# EmergencyCaller.net
KiCad netlist of a schematic drawn in Altium Designer
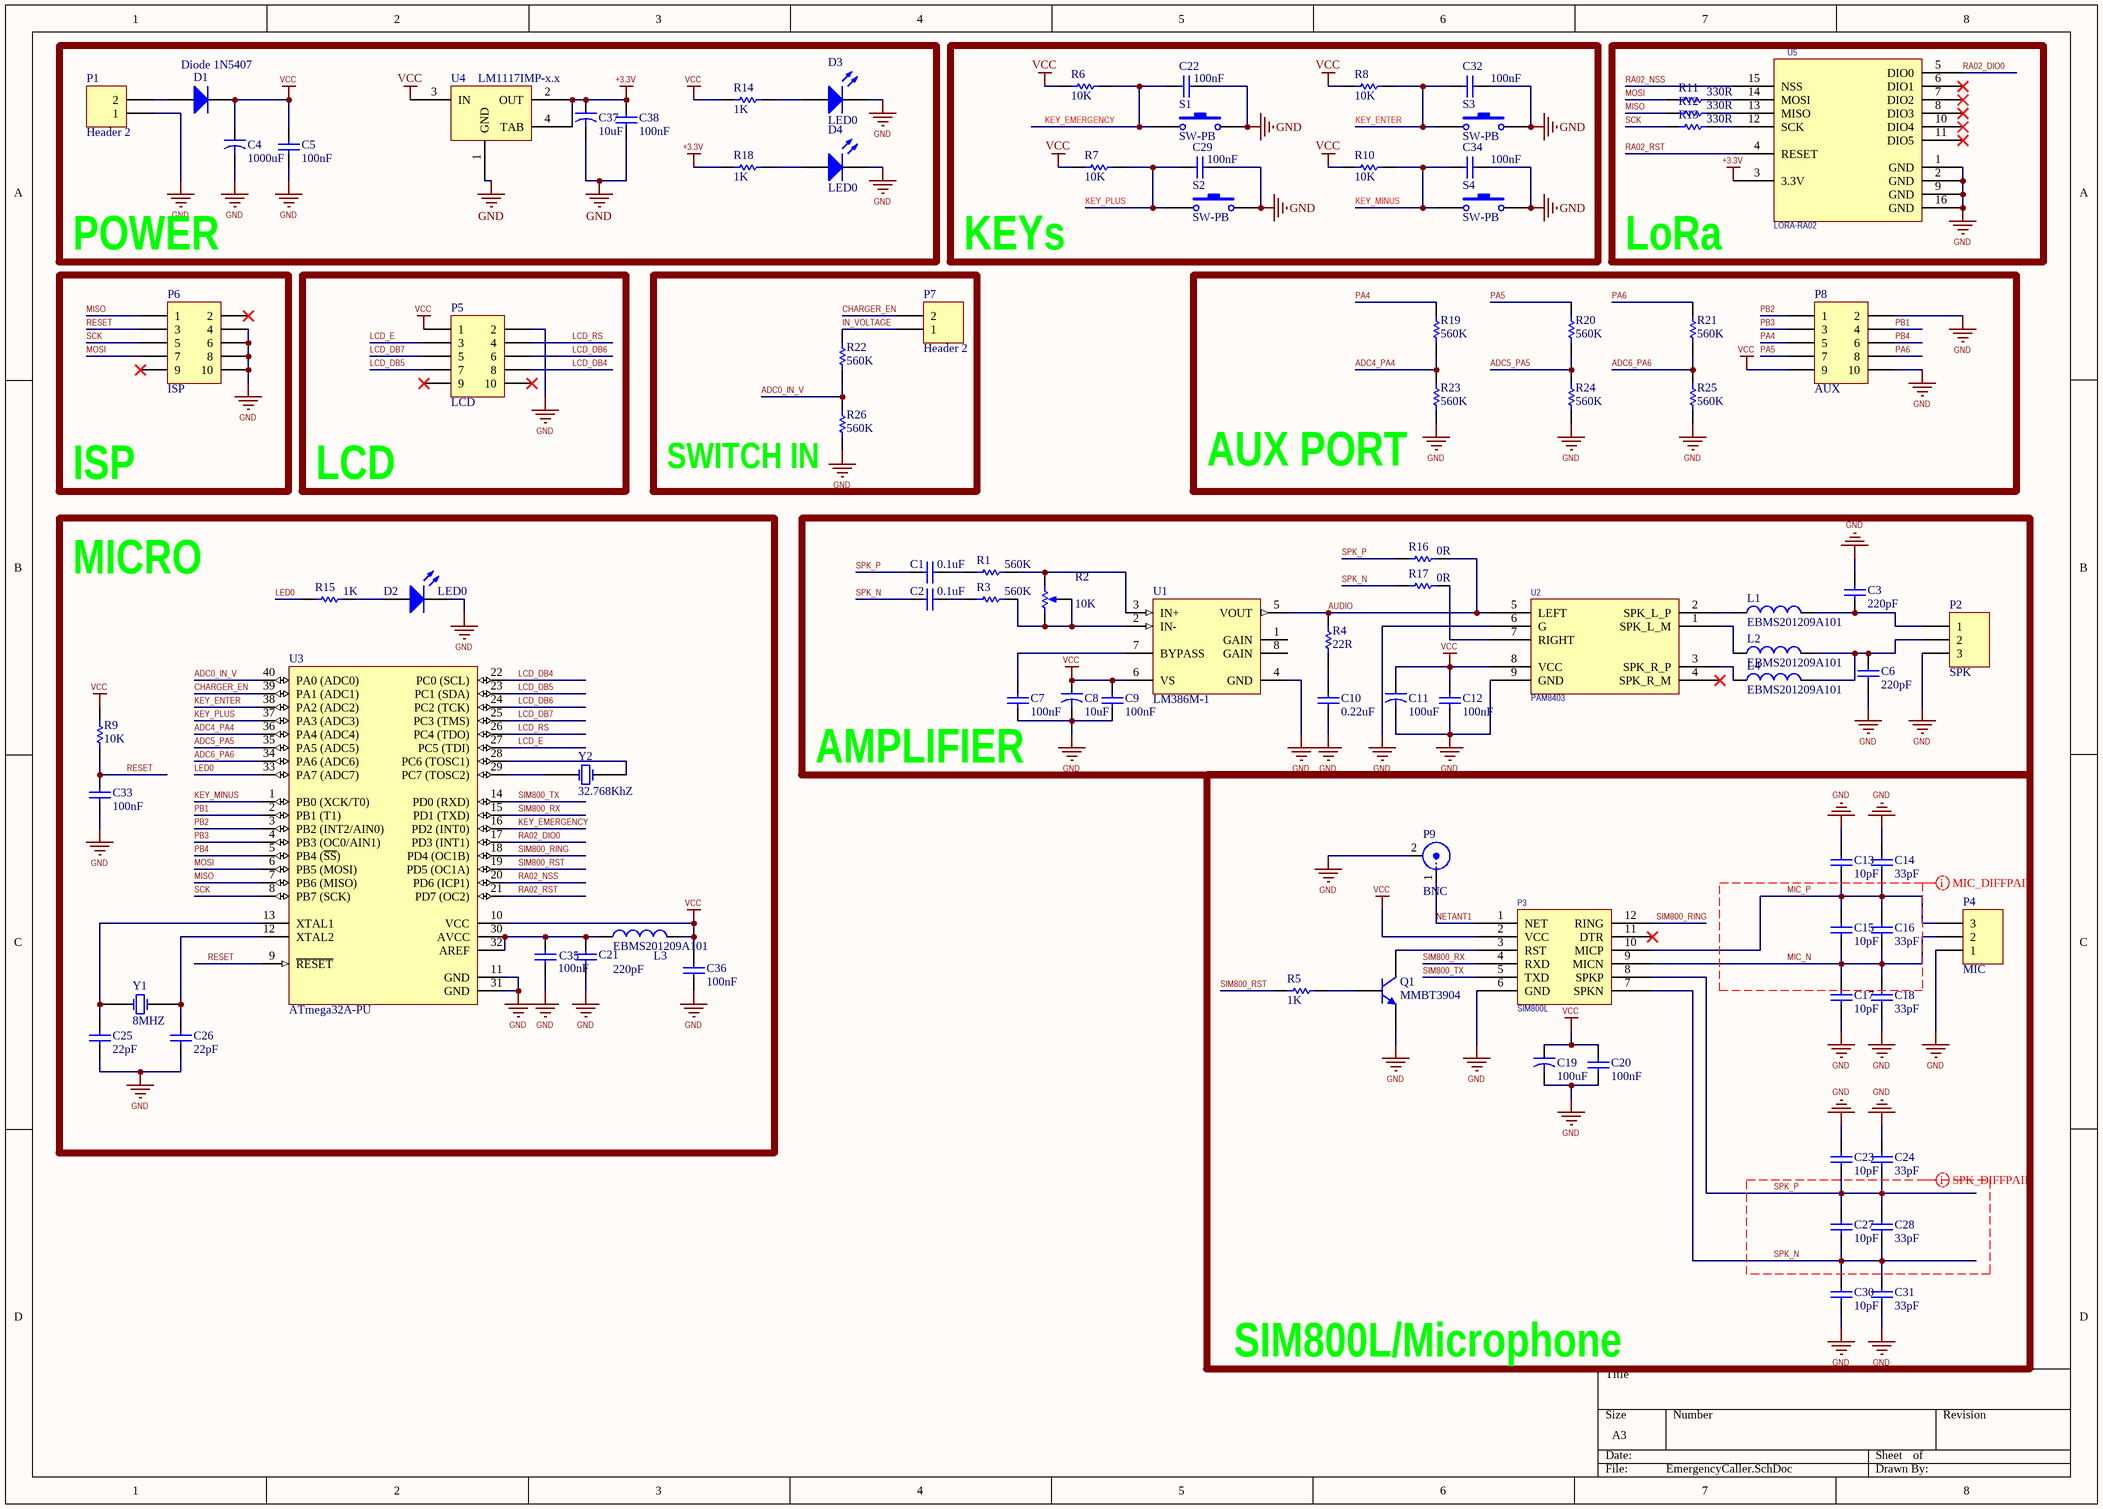
[diagram p0: EmergencyCaller.SchDoc]

(export (version "E")
  (design (tool "Eeschema 10.0.6"))
  (components
    (comp (ref "C1")
      (value "0.1uF")
      (footprint "CAP0805")
      (description "Capacitor")
      (fields (field (name "PUBLISHER") "Altium Limited"))
      (libsource (lib "Miscellaneous Devices") (part "Cap"))
    )
    (comp (ref "C2")
      (value "0.1uF")
      (footprint "CAP0805")
      (description "Capacitor")
      (fields (field (name "PUBLISHER") "Altium Limited"))
      (libsource (lib "Miscellaneous Devices") (part "Cap"))
    )
    (comp (ref "C3")
      (value "220pF")
      (footprint "CAP0805")
      (description "Capacitor")
      (fields (field (name "PUBLISHER") "Altium Limited"))
      (libsource (lib "Miscellaneous Devices") (part "Cap"))
    )
    (comp (ref "C4")
      (value "1000uF")
      (footprint "Cap electrolitic radial 10x16-5")
      (description "Capacitor")
      (fields (field (name "PUBLISHER") "Altium Limited"))
      (libsource (lib "Miscellaneous Devices") (part "Cap2"))
    )
    (comp (ref "C5")
      (value "100nF")
      (footprint "CAP0805")
      (description "Capacitor")
      (fields (field (name "PUBLISHER") "Altium Limited"))
      (libsource (lib "Miscellaneous Devices") (part "Cap"))
    )
    (comp (ref "C6")
      (value "220pF")
      (footprint "CAP0805")
      (description "Capacitor")
      (fields (field (name "PUBLISHER") "Altium Limited"))
      (libsource (lib "Miscellaneous Devices") (part "Cap"))
    )
    (comp (ref "C7")
      (value "100nF")
      (footprint "CAP0805")
      (description "Capacitor")
      (fields (field (name "PUBLISHER") "Altium Limited"))
      (libsource (lib "Miscellaneous Devices") (part "Cap"))
    )
    (comp (ref "C8")
      (value "10uF")
      (footprint "Cap electrolitic radial 5x11-2")
      (description "Capacitor")
      (fields (field (name "PUBLISHER") "Altium Limited"))
      (libsource (lib "Miscellaneous Devices") (part "Cap2"))
    )
    (comp (ref "C9")
      (value "100nF")
      (footprint "CAP0805")
      (description "Capacitor")
      (fields (field (name "PUBLISHER") "Altium Limited"))
      (libsource (lib "Miscellaneous Devices") (part "Cap"))
    )
    (comp (ref "C10")
      (value "0.22uF")
      (footprint "CAP0805")
      (description "Capacitor")
      (fields (field (name "PUBLISHER") "Altium Limited"))
      (libsource (lib "Miscellaneous Devices") (part "Cap"))
    )
    (comp (ref "C11")
      (value "100uF")
      (footprint "Cap electrolitic radial 10x16-5")
      (description "Capacitor")
      (fields (field (name "PUBLISHER") "Altium Limited"))
      (libsource (lib "Miscellaneous Devices") (part "Cap2"))
    )
    (comp (ref "C12")
      (value "100nF")
      (footprint "CAP0805")
      (description "Capacitor")
      (fields (field (name "PUBLISHER") "Altium Limited"))
      (libsource (lib "Miscellaneous Devices") (part "Cap"))
    )
    (comp (ref "C13")
      (value "10pF")
      (footprint "CAP0805")
      (description "Capacitor")
      (fields (field (name "PUBLISHER") "Altium Limited"))
      (libsource (lib "Miscellaneous Devices") (part "Cap"))
    )
    (comp (ref "C14")
      (value "33pF")
      (footprint "CAP0805")
      (description "Capacitor")
      (fields (field (name "PUBLISHER") "Altium Limited"))
      (libsource (lib "Miscellaneous Devices") (part "Cap"))
    )
    (comp (ref "C15")
      (value "10pF")
      (footprint "CAP0805")
      (description "Capacitor")
      (fields (field (name "PUBLISHER") "Altium Limited"))
      (libsource (lib "Miscellaneous Devices") (part "Cap"))
    )
    (comp (ref "C16")
      (value "33pF")
      (footprint "CAP0805")
      (description "Capacitor")
      (fields (field (name "PUBLISHER") "Altium Limited"))
      (libsource (lib "Miscellaneous Devices") (part "Cap"))
    )
    (comp (ref "C17")
      (value "10pF")
      (footprint "CAP0805")
      (description "Capacitor")
      (fields (field (name "PUBLISHER") "Altium Limited"))
      (libsource (lib "Miscellaneous Devices") (part "Cap"))
    )
    (comp (ref "C18")
      (value "33pF")
      (footprint "CAP0805")
      (description "Capacitor")
      (fields (field (name "PUBLISHER") "Altium Limited"))
      (libsource (lib "Miscellaneous Devices") (part "Cap"))
    )
    (comp (ref "C19")
      (value "100uF")
      (footprint "Cap electrolitic radial 10x16-5")
      (description "Capacitor")
      (fields (field (name "PUBLISHER") "Altium Limited"))
      (libsource (lib "Miscellaneous Devices") (part "Cap2"))
    )
    (comp (ref "C20")
      (value "100nF")
      (footprint "CAP0805")
      (description "Capacitor")
      (fields (field (name "PUBLISHER") "Altium Limited"))
      (libsource (lib "Miscellaneous Devices") (part "Cap"))
    )
    (comp (ref "C21")
      (value "220pF")
      (footprint "CAP0805")
      (description "Capacitor")
      (fields (field (name "PUBLISHER") "Altium Limited"))
      (libsource (lib "Miscellaneous Devices") (part "Cap"))
    )
    (comp (ref "C22")
      (value "100nF")
      (footprint "CAP0805")
      (description "Capacitor")
      (fields (field (name "Comment") "Cap") (field (name "PUBLISHER") "Altium Limited"))
      (libsource (lib "Miscellaneous Devices") (part "Cap"))
    )
    (comp (ref "C23")
      (value "10pF")
      (footprint "CAP0805")
      (description "Capacitor")
      (fields (field (name "PUBLISHER") "Altium Limited"))
      (libsource (lib "Miscellaneous Devices") (part "Cap"))
    )
    (comp (ref "C24")
      (value "33pF")
      (footprint "CAP0805")
      (description "Capacitor")
      (fields (field (name "PUBLISHER") "Altium Limited"))
      (libsource (lib "Miscellaneous Devices") (part "Cap"))
    )
    (comp (ref "C25")
      (value "22pF")
      (footprint "CAP0805")
      (description "Capacitor")
      (fields (field (name "PUBLISHER") "Altium Limited"))
      (libsource (lib "Miscellaneous Devices") (part "Cap"))
    )
    (comp (ref "C26")
      (value "22pF")
      (footprint "CAP0805")
      (description "Capacitor")
      (fields (field (name "PUBLISHER") "Altium Limited"))
      (libsource (lib "Miscellaneous Devices") (part "Cap"))
    )
    (comp (ref "C27")
      (value "10pF")
      (footprint "CAP0805")
      (description "Capacitor")
      (fields (field (name "PUBLISHER") "Altium Limited"))
      (libsource (lib "Miscellaneous Devices") (part "Cap"))
    )
    (comp (ref "C28")
      (value "33pF")
      (footprint "CAP0805")
      (description "Capacitor")
      (fields (field (name "PUBLISHER") "Altium Limited"))
      (libsource (lib "Miscellaneous Devices") (part "Cap"))
    )
    (comp (ref "C29")
      (value "100nF")
      (footprint "CAP0805")
      (description "Capacitor")
      (fields (field (name "Comment") "Cap") (field (name "PUBLISHER") "Altium Limited"))
      (libsource (lib "Miscellaneous Devices") (part "Cap"))
    )
    (comp (ref "C30")
      (value "10pF")
      (footprint "CAP0805")
      (description "Capacitor")
      (fields (field (name "PUBLISHER") "Altium Limited"))
      (libsource (lib "Miscellaneous Devices") (part "Cap"))
    )
    (comp (ref "C31")
      (value "33pF")
      (footprint "CAP0805")
      (description "Capacitor")
      (fields (field (name "PUBLISHER") "Altium Limited"))
      (libsource (lib "Miscellaneous Devices") (part "Cap"))
    )
    (comp (ref "C32")
      (value "100nF")
      (footprint "CAP0805")
      (description "Capacitor")
      (fields (field (name "Comment") "Cap") (field (name "PUBLISHER") "Altium Limited"))
      (libsource (lib "Miscellaneous Devices") (part "Cap"))
    )
    (comp (ref "C33")
      (value "100nF")
      (footprint "CAP0805")
      (description "Capacitor")
      (fields (field (name "PUBLISHER") "Altium Limited"))
      (libsource (lib "Miscellaneous Devices") (part "Cap"))
    )
    (comp (ref "C34")
      (value "100nF")
      (footprint "CAP0805")
      (description "Capacitor")
      (fields (field (name "Comment") "Cap") (field (name "PUBLISHER") "Altium Limited"))
      (libsource (lib "Miscellaneous Devices") (part "Cap"))
    )
    (comp (ref "C35")
      (value "100nF")
      (footprint "CAP0805")
      (description "Capacitor")
      (fields (field (name "Comment") "Cap") (field (name "PUBLISHER") "Altium Limited"))
      (libsource (lib "Miscellaneous Devices") (part "Cap"))
    )
    (comp (ref "C36")
      (value "100nF")
      (footprint "CAP0805")
      (description "Capacitor")
      (fields (field (name "PUBLISHER") "Altium Limited"))
      (libsource (lib "Miscellaneous Devices") (part "Cap"))
    )
    (comp (ref "C37")
      (value "10uF")
      (footprint "Cap electrolitic radial 5x11-2")
      (description "Capacitor")
      (fields (field (name "PUBLISHER") "Altium Limited"))
      (libsource (lib "Miscellaneous Devices") (part "Cap2"))
    )
    (comp (ref "C38")
      (value "100nF")
      (footprint "CAP0805")
      (description "Capacitor")
      (fields (field (name "PUBLISHER") "Altium Limited"))
      (libsource (lib "Miscellaneous Devices") (part "Cap"))
    )
    (comp (ref "D1")
      (value "Diode 1N5407")
      (footprint "1N5408 DO-201AD")
      (description "3 Amp Medium Power Silicon Rectifier Diode")
      (fields (field (name "PUBLISHER") "Altium Limited"))
      (libsource (lib "Miscellaneous Devices") (part "Diode 1N5407"))
    )
    (comp (ref "D2")
      (value "LED0")
      (footprint "LED_0805")
      (description "Typical INFRARED GaAs LED")
      (fields (field (name "PUBLISHER") "Altium Limited"))
      (libsource (lib "Miscellaneous Devices") (part "LED0"))
    )
    (comp (ref "D3")
      (value "LED0")
      (footprint "LED_0805")
      (description "Typical INFRARED GaAs LED")
      (fields (field (name "PUBLISHER") "Altium Limited"))
      (libsource (lib "Miscellaneous Devices") (part "LED0"))
    )
    (comp (ref "D4")
      (value "LED0")
      (footprint "LED_0805")
      (description "Typical INFRARED GaAs LED")
      (fields (field (name "PUBLISHER") "Altium Limited"))
      (libsource (lib "Miscellaneous Devices") (part "LED0"))
    )
    (comp (ref "L1")
      (value "EBMS201209A101")
      (footprint "IND0805")
      (description "Inductor")
      (fields (field (name "PUBLISHER") "Altium Limited"))
      (libsource (lib "Miscellaneous Devices") (part "Inductor"))
    )
    (comp (ref "L2")
      (value "EBMS201209A101")
      (footprint "IND0805")
      (description "Inductor")
      (fields (field (name "PUBLISHER") "Altium Limited"))
      (libsource (lib "Miscellaneous Devices") (part "Inductor"))
    )
    (comp (ref "L3")
      (value "EBMS201209A101")
      (footprint "IND0805")
      (description "Inductor")
      (fields (field (name "PUBLISHER") "Altium Limited"))
      (libsource (lib "Miscellaneous Devices") (part "Inductor"))
    )
    (comp (ref "L4")
      (value "EBMS201209A101")
      (footprint "IND0805")
      (description "Inductor")
      (fields (field (name "PUBLISHER") "Altium Limited"))
      (libsource (lib "Miscellaneous Devices") (part "Inductor"))
    )
    (comp (ref "P1")
      (value "Header 2")
      (footprint "KF301 2PIN")
      (description "Header, 2-Pin")
      (fields (field (name "PUBLISHER") "Altium Limited"))
      (libsource (lib "Miscellaneous Connectors") (part "Header 2"))
    )
    (comp (ref "P2")
      (value "SPK")
      (footprint "KF301 3PIN")
      (description "Header, 3-Pin")
      (fields (field (name "PUBLISHER") "Altium Limited"))
      (libsource (lib "Miscellaneous Connectors") (part "Header 3"))
    )
    (comp (ref "P3")
      (value "SIM800L")
      (footprint "SIM800L_MODULE_DoublePin")
      (description "Header, 2-Pin")
      (fields (field (name "PUBLISHER") "Altium Limited"))
      (libsource (lib "Mofidi3D") (part "sim800L_Module"))
    )
    (comp (ref "P4")
      (value "MIC")
      (footprint "KF301 3PIN")
      (description "Header, 3-Pin")
      (fields (field (name "PUBLISHER") "Altium Limited"))
      (libsource (lib "") (part "Header 3_1"))
    )
    (comp (ref "P5")
      (value "LCD")
      (footprint "IDC2.54-10PIN")
      (description "Header, 5-Pin, Dual row")
      (fields (field (name "PUBLISHER") "Altium Limited"))
      (libsource (lib "Miscellaneous Connectors") (part "Header 5X2"))
    )
    (comp (ref "P6")
      (value "ISP")
      (footprint "IDC2.54-10PIN")
      (description "Header, 5-Pin, Dual row")
      (fields (field (name "PUBLISHER") "Altium Limited"))
      (libsource (lib "Miscellaneous Connectors") (part "Header 5X2"))
    )
    (comp (ref "P7")
      (value "Header 2")
      (footprint "KF301 2PIN")
      (description "Header, 2-Pin")
      (fields (field (name "PUBLISHER") "Altium Limited"))
      (libsource (lib "") (part "Header 2_1"))
    )
    (comp (ref "P8")
      (value "AUX")
      (footprint "HDR2x5")
      (description "Header, 5-Pin, Dual row")
      (fields (field (name "PUBLISHER") "Altium Limited"))
      (libsource (lib "Miscellaneous Connectors") (part "Header 5X2"))
    )
    (comp (ref "P9")
      (value "BNC")
      (footprint "SMA_RA_F")
      (description "BNC Elbow Connector")
      (fields (field (name "PUBLISHER") "Altium Limited"))
      (libsource (lib "Miscellaneous Connectors") (part "BNC"))
    )
    (comp (ref "Q1")
      (value "MMBT3904")
      (footprint "SOT23_N")
      (description "NPN Switching Transistor")
      (fields (field (name "PUBLISHER") "Altium Limited"))
      (libsource (lib "Philips Discrete BJT - Low Power") (part "MMBT3904"))
    )
    (comp (ref "R1")
      (value "560K")
      (footprint "RES0805")
      (description "Resistor")
      (fields (field (name "PUBLISHER") "Altium Limited"))
      (libsource (lib "Miscellaneous Devices") (part "Res1"))
    )
    (comp (ref "R2")
      (value "10K")
      (footprint "MULTITURN_TRIMMER_3296")
      (description "Potentiometer")
      (fields (field (name "Comment") "RPot") (field (name "PUBLISHER") "Altium Limited"))
      (libsource (lib "Miscellaneous Devices") (part "RPot"))
    )
    (comp (ref "R3")
      (value "560K")
      (footprint "RES0805")
      (description "Resistor")
      (fields (field (name "PUBLISHER") "Altium Limited"))
      (libsource (lib "Miscellaneous Devices") (part "Res1"))
    )
    (comp (ref "R4")
      (value "22R")
      (footprint "RES0805")
      (description "Resistor")
      (fields (field (name "PUBLISHER") "Altium Limited"))
      (libsource (lib "Miscellaneous Devices") (part "Res1"))
    )
    (comp (ref "R5")
      (value "1K")
      (footprint "RES0805")
      (description "Resistor")
      (fields (field (name "PUBLISHER") "Altium Limited"))
      (libsource (lib "Miscellaneous Devices") (part "Res1"))
    )
    (comp (ref "R6")
      (value "10K")
      (footprint "RES0805")
      (description "Resistor")
      (fields (field (name "Comment") "Res1") (field (name "PUBLISHER") "Altium Limited"))
      (libsource (lib "Miscellaneous Devices") (part "Res1"))
    )
    (comp (ref "R7")
      (value "10K")
      (footprint "RES0805")
      (description "Resistor")
      (fields (field (name "Comment") "Res1") (field (name "PUBLISHER") "Altium Limited"))
      (libsource (lib "Miscellaneous Devices") (part "Res1"))
    )
    (comp (ref "R8")
      (value "10K")
      (footprint "RES0805")
      (description "Resistor")
      (fields (field (name "Comment") "Res1") (field (name "PUBLISHER") "Altium Limited"))
      (libsource (lib "Miscellaneous Devices") (part "Res1"))
    )
    (comp (ref "R9")
      (value "10K")
      (footprint "RES0805")
      (description "Resistor")
      (fields (field (name "PUBLISHER") "Altium Limited"))
      (libsource (lib "Miscellaneous Devices") (part "Res1"))
    )
    (comp (ref "R10")
      (value "10K")
      (footprint "RES0805")
      (description "Resistor")
      (fields (field (name "Comment") "Res1") (field (name "PUBLISHER") "Altium Limited"))
      (libsource (lib "Miscellaneous Devices") (part "Res1"))
    )
    (comp (ref "R11")
      (value "330R")
      (footprint "RES0805")
      (description "Resistor")
      (fields (field (name "PUBLISHER") "Altium Limited"))
      (libsource (lib "Miscellaneous Devices") (part "Res1"))
    )
    (comp (ref "R12")
      (value "330R")
      (footprint "RES0805")
      (description "Resistor")
      (fields (field (name "PUBLISHER") "Altium Limited"))
      (libsource (lib "Miscellaneous Devices") (part "Res1"))
    )
    (comp (ref "R13")
      (value "330R")
      (footprint "RES0805")
      (description "Resistor")
      (fields (field (name "PUBLISHER") "Altium Limited"))
      (libsource (lib "Miscellaneous Devices") (part "Res1"))
    )
    (comp (ref "R14")
      (value "1K")
      (footprint "RES0805")
      (description "Resistor")
      (fields (field (name "PUBLISHER") "Altium Limited"))
      (libsource (lib "Miscellaneous Devices") (part "Res1"))
    )
    (comp (ref "R15")
      (value "1K")
      (footprint "RES0805")
      (description "Resistor")
      (fields (field (name "PUBLISHER") "Altium Limited"))
      (libsource (lib "Miscellaneous Devices") (part "Res1"))
    )
    (comp (ref "R16")
      (value "0R")
      (footprint "RES0805")
      (description "Resistor")
      (fields (field (name "PUBLISHER") "Altium Limited"))
      (libsource (lib "Miscellaneous Devices") (part "Res1"))
    )
    (comp (ref "R17")
      (value "0R")
      (footprint "RES0805")
      (description "Resistor")
      (fields (field (name "PUBLISHER") "Altium Limited"))
      (libsource (lib "Miscellaneous Devices") (part "Res1"))
    )
    (comp (ref "R18")
      (value "1K")
      (footprint "RES0805")
      (description "Resistor")
      (fields (field (name "PUBLISHER") "Altium Limited"))
      (libsource (lib "Miscellaneous Devices") (part "Res1"))
    )
    (comp (ref "R19")
      (value "560K")
      (footprint "RES0805")
      (description "Resistor")
      (fields (field (name "PUBLISHER") "Altium Limited"))
      (libsource (lib "Miscellaneous Devices") (part "Res1"))
    )
    (comp (ref "R20")
      (value "560K")
      (footprint "RES0805")
      (description "Resistor")
      (fields (field (name "PUBLISHER") "Altium Limited"))
      (libsource (lib "Miscellaneous Devices") (part "Res1"))
    )
    (comp (ref "R21")
      (value "560K")
      (footprint "RES0805")
      (description "Resistor")
      (fields (field (name "PUBLISHER") "Altium Limited"))
      (libsource (lib "Miscellaneous Devices") (part "Res1"))
    )
    (comp (ref "R22")
      (value "560K")
      (footprint "RES0805")
      (description "Resistor")
      (fields (field (name "PUBLISHER") "Altium Limited"))
      (libsource (lib "Miscellaneous Devices") (part "Res1"))
    )
    (comp (ref "R23")
      (value "560K")
      (footprint "RES0805")
      (description "Resistor")
      (fields (field (name "PUBLISHER") "Altium Limited"))
      (libsource (lib "Miscellaneous Devices") (part "Res1"))
    )
    (comp (ref "R24")
      (value "560K")
      (footprint "RES0805")
      (description "Resistor")
      (fields (field (name "PUBLISHER") "Altium Limited"))
      (libsource (lib "Miscellaneous Devices") (part "Res1"))
    )
    (comp (ref "R25")
      (value "560K")
      (footprint "RES0805")
      (description "Resistor")
      (fields (field (name "PUBLISHER") "Altium Limited"))
      (libsource (lib "Miscellaneous Devices") (part "Res1"))
    )
    (comp (ref "R26")
      (value "560K")
      (footprint "RES0805")
      (description "Resistor")
      (fields (field (name "PUBLISHER") "Altium Limited"))
      (libsource (lib "Miscellaneous Devices") (part "Res1"))
    )
    (comp (ref "S1")
      (value "SW-PB")
      (footprint "KF301 2PIN")
      (description "Switch")
      (fields (field (name "PUBLISHER") "Altium Limited"))
      (libsource (lib "Miscellaneous Devices") (part "SW-PB"))
    )
    (comp (ref "S2")
      (value "SW-PB")
      (footprint "SW-4PIN")
      (description "Switch")
      (fields (field (name "PUBLISHER") "Altium Limited"))
      (libsource (lib "Miscellaneous Devices") (part "SW-PB"))
    )
    (comp (ref "S3")
      (value "SW-PB")
      (footprint "SW-4PIN")
      (description "Switch")
      (fields (field (name "PUBLISHER") "Altium Limited"))
      (libsource (lib "Miscellaneous Devices") (part "SW-PB"))
    )
    (comp (ref "S4")
      (value "SW-PB")
      (footprint "SW-4PIN")
      (description "Switch")
      (fields (field (name "PUBLISHER") "Altium Limited"))
      (libsource (lib "Miscellaneous Devices") (part "SW-PB"))
    )
    (comp (ref "U1")
      (value "LM386M-1")
      (footprint "SO-8N")
      (description "Low Voltage Audio Power Amplifier, 8-pin Narrow SOIC")
      (fields
        (field (name "MANUFACTURER") "National Semiconductor")
        (field (name "PUBLISHER") "Altium Limited")
      )
      (libsource (lib "NSC Audio") (part "LM386M-1"))
    )
    (comp (ref "U2")
      (value "PAM8403")
      (footprint "PAM8403_MODULE")
      (description "FILTERLESS 3W CLASS-D STEREO AUDIO AMPLIFIER")
      (fields (field (name "PUBLISHER") "Altium Limited"))
      (libsource (lib "Mofidi3D") (part "PAM8403_Module"))
    )
    (comp (ref "U3")
      (value "ATmega32A-PU")
      (footprint "40P6")
      (fields (field (name "PUBLISHER") "Altium Limited"))
      (libsource (lib "Atmel Microcontroller 8-Bit megaAVR") (part "ATmega32A-PU"))
    )
    (comp (ref "U4")
      (value "LM1117IMP-x.x")
      (footprint "SOT223_4")
      (description "x.x Volt, 800mA Low-Dropout Linear Regulator, 4-pin SOT-223")
      (fields (field (name "DESIGNER") "Abbas Basereh"))
      (libsource (lib "Mofidi3D") (part "LM1117IMP-x.x"))
    )
    (comp (ref "U5")
      (value "LORA-RA02")
      (footprint "RA02-LoRa-Module")
      (description "sx1278  Low Power Long Range Transceiver")
      (fields (field (name "PUBLISHER") "Altium Limited"))
      (libsource (lib "Mofidi3D") (part "LORA-RA02"))
    )
    (comp (ref "Y1")
      (value "8MHZ")
      (footprint "CRYSTAL Small")
      (description "XTAL Crystal")
      (fields (field (name "DESIGNER") "ABBAS BASEREH"))
      (libsource (lib "Mofidi3D") (part "XTAL_Crystal"))
    )
    (comp (ref "Y2")
      (value "32.768KhZ")
      (footprint "Crystal_NC308")
      (description "XTAL Crystal")
      (fields (field (name "DESIGNER") "ABBAS BASEREH"))
      (libsource (lib "Mofidi3D") (part "XTAL_Crystal"))
    )
  )
  (nets
    (net (code "1") (name "+3.3V") (class "Default")
      (node (ref "C37") (pin "1") (pinfunction "1_1") (pintype "passive"))
      (node (ref "C38") (pin "2") (pinfunction "2_2") (pintype "passive"))
      (node (ref "R18") (pin "1") (pinfunction "1_1") (pintype "passive"))
      (node (ref "U4") (pin "2") (pinfunction "OUT_2") (pintype "power_in"))
      (node (ref "U4") (pin "4") (pinfunction "TAB_4") (pintype "power_in"))
      (node (ref "U5") (pin "3") (pinfunction "3.3V_3") (pintype "passive"))
    )
    (net (code "2") (name "/ADC0_IN_V") (class "Default")
      (node (ref "R22") (pin "1") (pinfunction "1_1") (pintype "passive"))
      (node (ref "R26") (pin "2") (pinfunction "2_2") (pintype "passive"))
      (node (ref "U3") (pin "40") (pinfunction "PA0_(ADC0)_40") (pintype "bidirectional"))
    )
    (net (code "3") (name "/ADC4_PA4") (class "Default")
      (node (ref "R19") (pin "1") (pinfunction "1_1") (pintype "passive"))
      (node (ref "R23") (pin "2") (pinfunction "2_2") (pintype "passive"))
      (node (ref "U3") (pin "36") (pinfunction "PA4_(ADC4)_36") (pintype "bidirectional"))
    )
    (net (code "4") (name "/ADC5_PA5") (class "Default")
      (node (ref "R20") (pin "1") (pinfunction "1_1") (pintype "passive"))
      (node (ref "R24") (pin "2") (pinfunction "2_2") (pintype "passive"))
      (node (ref "U3") (pin "35") (pinfunction "PA5_(ADC5)_35") (pintype "bidirectional"))
    )
    (net (code "5") (name "/ADC6_PA6") (class "Default")
      (node (ref "R21") (pin "1") (pinfunction "1_1") (pintype "passive"))
      (node (ref "R25") (pin "2") (pinfunction "2_2") (pintype "passive"))
      (node (ref "U3") (pin "34") (pinfunction "PA6_(ADC6)_34") (pintype "bidirectional"))
    )
    (net (code "6") (name "/AUDIO") (class "Default")
      (node (ref "R16") (pin "1") (pinfunction "1_1") (pintype "passive"))
      (node (ref "R4") (pin "2") (pinfunction "2_2") (pintype "passive"))
      (node (ref "U1") (pin "5") (pinfunction "VOUT_5") (pintype "output"))
      (node (ref "U2") (pin "5") (pinfunction "LEFT_5") (pintype "passive"))
    )
    (net (code "7") (name "/CHARGER_EN") (class "Default")
      (node (ref "P7") (pin "2") (pinfunction "2_2") (pintype "passive"))
      (node (ref "U3") (pin "39") (pinfunction "PA1_(ADC1)_39") (pintype "bidirectional"))
    )
    (net (code "8") (name "/IN_VOLTAGE") (class "Default")
      (node (ref "P7") (pin "1") (pinfunction "1_1") (pintype "passive"))
      (node (ref "R22") (pin "2") (pinfunction "2_2") (pintype "passive"))
    )
    (net (code "9") (name "/KEY_EMERGENCY") (class "Default")
      (node (ref "C22") (pin "1") (pinfunction "1_1") (pintype "passive"))
      (node (ref "R6") (pin "1") (pinfunction "1_1") (pintype "passive"))
      (node (ref "S1") (pin "1") (pinfunction "1_1") (pintype "passive"))
      (node (ref "U3") (pin "16") (pinfunction "PD2_(INT0)_16") (pintype "bidirectional"))
    )
    (net (code "10") (name "/KEY_ENTER") (class "Default")
      (node (ref "C32") (pin "1") (pinfunction "1_1") (pintype "passive"))
      (node (ref "R8") (pin "1") (pinfunction "1_1") (pintype "passive"))
      (node (ref "S3") (pin "1") (pinfunction "1_1") (pintype "passive"))
      (node (ref "U3") (pin "38") (pinfunction "PA2_(ADC2)_38") (pintype "bidirectional"))
    )
    (net (code "11") (name "/KEY_MINUS") (class "Default")
      (node (ref "C34") (pin "1") (pinfunction "1_1") (pintype "passive"))
      (node (ref "R10") (pin "1") (pinfunction "1_1") (pintype "passive"))
      (node (ref "S4") (pin "1") (pinfunction "1_1") (pintype "passive"))
      (node (ref "U3") (pin "1") (pinfunction "PB0_(XCK/T0)_1") (pintype "bidirectional"))
    )
    (net (code "12") (name "/KEY_PLUS") (class "Default")
      (node (ref "C29") (pin "1") (pinfunction "1_1") (pintype "passive"))
      (node (ref "R7") (pin "1") (pinfunction "1_1") (pintype "passive"))
      (node (ref "S2") (pin "1") (pinfunction "1_1") (pintype "passive"))
      (node (ref "U3") (pin "37") (pinfunction "PA3_(ADC3)_37") (pintype "bidirectional"))
    )
    (net (code "13") (name "/LCD_DB4") (class "Default")
      (node (ref "P5") (pin "8") (pinfunction "8_8") (pintype "passive"))
      (node (ref "U3") (pin "22") (pinfunction "PC0_(SCL)_22") (pintype "bidirectional"))
    )
    (net (code "14") (name "/LCD_DB5") (class "Default")
      (node (ref "P5") (pin "7") (pinfunction "7_7") (pintype "passive"))
      (node (ref "U3") (pin "23") (pinfunction "PC1_(SDA)_23") (pintype "bidirectional"))
    )
    (net (code "15") (name "/LCD_DB6") (class "Default")
      (node (ref "P5") (pin "6") (pinfunction "6_6") (pintype "passive"))
      (node (ref "U3") (pin "24") (pinfunction "PC2_(TCK)_24") (pintype "bidirectional"))
    )
    (net (code "16") (name "/LCD_DB7") (class "Default")
      (node (ref "P5") (pin "5") (pinfunction "5_5") (pintype "passive"))
      (node (ref "U3") (pin "25") (pinfunction "PC3_(TMS)_25") (pintype "bidirectional"))
    )
    (net (code "17") (name "/LCD_E") (class "Default")
      (node (ref "P5") (pin "3") (pinfunction "3_3") (pintype "passive"))
      (node (ref "U3") (pin "27") (pinfunction "PC5_(TDI)_27") (pintype "bidirectional"))
    )
    (net (code "18") (name "/LCD_RS") (class "Default")
      (node (ref "P5") (pin "4") (pinfunction "4_4") (pintype "passive"))
      (node (ref "U3") (pin "26") (pinfunction "PC4_(TDO)_26") (pintype "bidirectional"))
    )
    (net (code "19") (name "/LED0") (class "Default")
      (node (ref "R15") (pin "1") (pinfunction "1_1") (pintype "passive"))
      (node (ref "U3") (pin "33") (pinfunction "PA7_(ADC7)_33") (pintype "bidirectional"))
    )
    (net (code "20") (name "/MIC_N") (class "Default")
      (node (ref "C15") (pin "1") (pinfunction "1_1") (pintype "passive"))
      (node (ref "C16") (pin "1") (pinfunction "1_1") (pintype "passive"))
      (node (ref "C17") (pin "2") (pinfunction "2_2") (pintype "passive"))
      (node (ref "C18") (pin "2") (pinfunction "2_2") (pintype "passive"))
      (node (ref "P3") (pin "9") (pinfunction "MICN_9") (pintype "passive"))
      (node (ref "P4") (pin "2") (pinfunction "2_2") (pintype "passive"))
    )
    (net (code "21") (name "/MIC_P") (class "Default")
      (node (ref "C13") (pin "1") (pinfunction "1_1") (pintype "passive"))
      (node (ref "C14") (pin "1") (pinfunction "1_1") (pintype "passive"))
      (node (ref "C15") (pin "2") (pinfunction "2_2") (pintype "passive"))
      (node (ref "C16") (pin "2") (pinfunction "2_2") (pintype "passive"))
      (node (ref "P3") (pin "10") (pinfunction "MICP_10") (pintype "passive"))
      (node (ref "P4") (pin "3") (pinfunction "3_3") (pintype "passive"))
    )
    (net (code "22") (name "/MISO") (class "Default")
      (node (ref "P6") (pin "1") (pinfunction "1_1") (pintype "passive"))
      (node (ref "R12") (pin "2") (pinfunction "2_2") (pintype "passive"))
      (node (ref "U3") (pin "7") (pinfunction "PB6_(MISO)_7") (pintype "bidirectional"))
    )
    (net (code "23") (name "/MOSI") (class "Default")
      (node (ref "P6") (pin "7") (pinfunction "7_7") (pintype "passive"))
      (node (ref "R11") (pin "2") (pinfunction "2_2") (pintype "passive"))
      (node (ref "U3") (pin "6") (pinfunction "PB5_(MOSI)_6") (pintype "bidirectional"))
    )
    (net (code "24") (name "/NETANT1") (class "Default")
      (node (ref "P3") (pin "1") (pinfunction "NET_1") (pintype "passive"))
      (node (ref "P9") (pin "1") (pinfunction "X_1") (pintype "passive"))
    )
    (net (code "25") (name "/PA4") (class "Default")
      (node (ref "P8") (pin "5") (pinfunction "5_5") (pintype "passive"))
      (node (ref "R19") (pin "2") (pinfunction "2_2") (pintype "passive"))
    )
    (net (code "26") (name "/PA5") (class "Default")
      (node (ref "P8") (pin "7") (pinfunction "7_7") (pintype "passive"))
      (node (ref "R20") (pin "2") (pinfunction "2_2") (pintype "passive"))
    )
    (net (code "27") (name "/PA6") (class "Default")
      (node (ref "P8") (pin "8") (pinfunction "8_8") (pintype "passive"))
      (node (ref "R21") (pin "2") (pinfunction "2_2") (pintype "passive"))
    )
    (net (code "28") (name "/PB1") (class "Default")
      (node (ref "P8") (pin "4") (pinfunction "4_4") (pintype "passive"))
      (node (ref "U3") (pin "2") (pinfunction "PB1_(T1)_2") (pintype "bidirectional"))
    )
    (net (code "29") (name "/PB2") (class "Default")
      (node (ref "P8") (pin "1") (pinfunction "1_1") (pintype "passive"))
      (node (ref "U3") (pin "3") (pinfunction "PB2_(INT2/AIN0)_3") (pintype "bidirectional"))
    )
    (net (code "30") (name "/PB3") (class "Default")
      (node (ref "P8") (pin "3") (pinfunction "3_3") (pintype "passive"))
      (node (ref "U3") (pin "4") (pinfunction "PB3_(OC0/AIN1)_4") (pintype "bidirectional"))
    )
    (net (code "31") (name "/PB4") (class "Default")
      (node (ref "P8") (pin "6") (pinfunction "6_6") (pintype "passive"))
      (node (ref "U3") (pin "5") (pinfunction "PB4_(~{SS})_5") (pintype "bidirectional"))
    )
    (net (code "32") (name "/RA02_DIO0") (class "Default")
      (node (ref "U3") (pin "17") (pinfunction "PD3_(INT1)_17") (pintype "bidirectional"))
      (node (ref "U5") (pin "5") (pinfunction "DIO0_5") (pintype "passive"))
    )
    (net (code "33") (name "/RA02_NSS") (class "Default")
      (node (ref "U3") (pin "20") (pinfunction "PD6_(ICP1)_20") (pintype "bidirectional"))
      (node (ref "U5") (pin "15") (pinfunction "NSS_15") (pintype "passive"))
    )
    (net (code "34") (name "/RA02_RST") (class "Default")
      (node (ref "U3") (pin "21") (pinfunction "PD7_(OC2)_21") (pintype "bidirectional"))
      (node (ref "U5") (pin "4") (pinfunction "RESET_4") (pintype "passive"))
    )
    (net (code "35") (name "/RESET") (class "Default")
      (node (ref "C33") (pin "2") (pinfunction "2_2") (pintype "passive"))
      (node (ref "P6") (pin "3") (pinfunction "3_3") (pintype "passive"))
      (node (ref "R9") (pin "1") (pinfunction "1_1") (pintype "passive"))
      (node (ref "U3") (pin "9") (pinfunction "~{RESET}_9") (pintype "input"))
    )
    (net (code "36") (name "/SCK") (class "Default")
      (node (ref "P6") (pin "5") (pinfunction "5_5") (pintype "passive"))
      (node (ref "R13") (pin "2") (pinfunction "2_2") (pintype "passive"))
      (node (ref "U3") (pin "8") (pinfunction "PB7_(SCK)_8") (pintype "bidirectional"))
    )
    (net (code "37") (name "/SIM800_RING") (class "Default")
      (node (ref "P3") (pin "12") (pinfunction "RING_12") (pintype "passive"))
      (node (ref "U3") (pin "18") (pinfunction "PD4_(OC1B)_18") (pintype "bidirectional"))
    )
    (net (code "38") (name "/SIM800_RST") (class "Default")
      (node (ref "R5") (pin "1") (pinfunction "1_1") (pintype "passive"))
      (node (ref "U3") (pin "19") (pinfunction "PD5_(OC1A)_19") (pintype "bidirectional"))
    )
    (net (code "39") (name "/SIM800_RX") (class "Default")
      (node (ref "P3") (pin "4") (pinfunction "RXD_4") (pintype "passive"))
      (node (ref "U3") (pin "15") (pinfunction "PD1_(TXD)_15") (pintype "bidirectional"))
    )
    (net (code "40") (name "/SIM800_TX") (class "Default")
      (node (ref "P3") (pin "5") (pinfunction "TXD_5") (pintype "passive"))
      (node (ref "U3") (pin "14") (pinfunction "PD0_(RXD)_14") (pintype "bidirectional"))
    )
    (net (code "41") (name "/SPK_N") (class "Default")
      (node (ref "C2") (pin "2") (pinfunction "2_2") (pintype "passive"))
      (node (ref "C27") (pin "1") (pinfunction "1_1") (pintype "passive"))
      (node (ref "C28") (pin "1") (pinfunction "1_1") (pintype "passive"))
      (node (ref "C30") (pin "2") (pinfunction "2_2") (pintype "passive"))
      (node (ref "C31") (pin "2") (pinfunction "2_2") (pintype "passive"))
      (node (ref "P3") (pin "7") (pinfunction "SPKN_7") (pintype "passive"))
      (node (ref "R17") (pin "2") (pinfunction "2_2") (pintype "passive"))
    )
    (net (code "42") (name "/SPK_P") (class "Default")
      (node (ref "C1") (pin "2") (pinfunction "2_2") (pintype "passive"))
      (node (ref "C23") (pin "1") (pinfunction "1_1") (pintype "passive"))
      (node (ref "C24") (pin "1") (pinfunction "1_1") (pintype "passive"))
      (node (ref "C27") (pin "2") (pinfunction "2_2") (pintype "passive"))
      (node (ref "C28") (pin "2") (pinfunction "2_2") (pintype "passive"))
      (node (ref "P3") (pin "8") (pinfunction "SPKP_8") (pintype "passive"))
      (node (ref "R16") (pin "2") (pinfunction "2_2") (pintype "passive"))
    )
    (net (code "43") (name "GND") (class "Default")
      (node (ref "C10") (pin "2") (pinfunction "2_2") (pintype "passive"))
      (node (ref "C11") (pin "2") (pinfunction "2_2") (pintype "passive"))
      (node (ref "C12") (pin "1") (pinfunction "1_1") (pintype "passive"))
      (node (ref "C13") (pin "2") (pinfunction "2_2") (pintype "passive"))
      (node (ref "C14") (pin "2") (pinfunction "2_2") (pintype "passive"))
      (node (ref "C17") (pin "1") (pinfunction "1_1") (pintype "passive"))
      (node (ref "C18") (pin "1") (pinfunction "1_1") (pintype "passive"))
      (node (ref "C19") (pin "2") (pinfunction "2_2") (pintype "passive"))
      (node (ref "C20") (pin "1") (pinfunction "1_1") (pintype "passive"))
      (node (ref "C21") (pin "2") (pinfunction "2_2") (pintype "passive"))
      (node (ref "C22") (pin "2") (pinfunction "2_2") (pintype "passive"))
      (node (ref "C23") (pin "2") (pinfunction "2_2") (pintype "passive"))
      (node (ref "C24") (pin "2") (pinfunction "2_2") (pintype "passive"))
      (node (ref "C25") (pin "2") (pinfunction "2_2") (pintype "passive"))
      (node (ref "C26") (pin "2") (pinfunction "2_2") (pintype "passive"))
      (node (ref "C29") (pin "2") (pinfunction "2_2") (pintype "passive"))
      (node (ref "C3") (pin "1") (pinfunction "1_1") (pintype "passive"))
      (node (ref "C30") (pin "1") (pinfunction "1_1") (pintype "passive"))
      (node (ref "C31") (pin "1") (pinfunction "1_1") (pintype "passive"))
      (node (ref "C32") (pin "2") (pinfunction "2_2") (pintype "passive"))
      (node (ref "C33") (pin "1") (pinfunction "1_1") (pintype "passive"))
      (node (ref "C34") (pin "2") (pinfunction "2_2") (pintype "passive"))
      (node (ref "C35") (pin "1") (pinfunction "1_1") (pintype "passive"))
      (node (ref "C36") (pin "1") (pinfunction "1_1") (pintype "passive"))
      (node (ref "C37") (pin "2") (pinfunction "2_2") (pintype "passive"))
      (node (ref "C38") (pin "1") (pinfunction "1_1") (pintype "passive"))
      (node (ref "C4") (pin "2") (pinfunction "2_2") (pintype "passive"))
      (node (ref "C5") (pin "1") (pinfunction "1_1") (pintype "passive"))
      (node (ref "C6") (pin "1") (pinfunction "1_1") (pintype "passive"))
      (node (ref "C7") (pin "1") (pinfunction "1_1") (pintype "passive"))
      (node (ref "C8") (pin "2") (pinfunction "2_2") (pintype "passive"))
      (node (ref "C9") (pin "1") (pinfunction "1_1") (pintype "passive"))
      (node (ref "D2") (pin "2") (pinfunction "K_2") (pintype "passive"))
      (node (ref "D3") (pin "2") (pinfunction "K_2") (pintype "passive"))
      (node (ref "D4") (pin "2") (pinfunction "K_2") (pintype "passive"))
      (node (ref "P1") (pin "1") (pinfunction "1_1") (pintype "passive"))
      (node (ref "P2") (pin "3") (pinfunction "3_3") (pintype "passive"))
      (node (ref "P3") (pin "6") (pinfunction "GND_6") (pintype "passive"))
      (node (ref "P4") (pin "1") (pinfunction "1_1") (pintype "passive"))
      (node (ref "P5") (pin "2") (pinfunction "2_2") (pintype "passive"))
      (node (ref "P6") (pin "10") (pinfunction "10_10") (pintype "passive"))
      (node (ref "P6") (pin "4") (pinfunction "4_4") (pintype "passive"))
      (node (ref "P6") (pin "6") (pinfunction "6_6") (pintype "passive"))
      (node (ref "P6") (pin "8") (pinfunction "8_8") (pintype "passive"))
      (node (ref "P8") (pin "10") (pinfunction "10_10") (pintype "passive"))
      (node (ref "P8") (pin "2") (pinfunction "2_2") (pintype "passive"))
      (node (ref "P9") (pin "2") (pinfunction "Y_2") (pintype "passive"))
      (node (ref "Q1") (pin "2") (pinfunction "E_2") (pintype "passive"))
      (node (ref "R23") (pin "1") (pinfunction "1_1") (pintype "passive"))
      (node (ref "R24") (pin "1") (pinfunction "1_1") (pintype "passive"))
      (node (ref "R25") (pin "1") (pinfunction "1_1") (pintype "passive"))
      (node (ref "R26") (pin "1") (pinfunction "1_1") (pintype "passive"))
      (node (ref "S1") (pin "2") (pinfunction "2_2") (pintype "passive"))
      (node (ref "S2") (pin "2") (pinfunction "2_2") (pintype "passive"))
      (node (ref "S3") (pin "2") (pinfunction "2_2") (pintype "passive"))
      (node (ref "S4") (pin "2") (pinfunction "2_2") (pintype "passive"))
      (node (ref "U1") (pin "4") (pinfunction "GND_4") (pintype "power_in"))
      (node (ref "U2") (pin "6") (pinfunction "G_6") (pintype "passive"))
      (node (ref "U2") (pin "9") (pinfunction "GND_9") (pintype "passive"))
      (node (ref "U3") (pin "11") (pinfunction "GND_11") (pintype "power_in"))
      (node (ref "U3") (pin "31") (pinfunction "GND_31") (pintype "power_in"))
      (node (ref "U4") (pin "1") (pinfunction "GND_1") (pintype "power_in"))
      (node (ref "U5") (pin "1") (pinfunction "GND_1") (pintype "passive"))
      (node (ref "U5") (pin "16") (pinfunction "GND_16") (pintype "passive"))
      (node (ref "U5") (pin "2") (pinfunction "GND_2") (pintype "passive"))
      (node (ref "U5") (pin "9") (pinfunction "GND_9") (pintype "passive"))
    )
    (net (code "44") (name "Net-(C1-Pad1)") (class "Default")
      (node (ref "C1") (pin "1") (pinfunction "1_1") (pintype "passive"))
      (node (ref "R1") (pin "1") (pinfunction "1_1") (pintype "passive"))
    )
    (net (code "45") (name "Net-(C2-Pad1)") (class "Default")
      (node (ref "C2") (pin "1") (pinfunction "1_1") (pintype "passive"))
      (node (ref "R3") (pin "1") (pinfunction "1_1") (pintype "passive"))
    )
    (net (code "46") (name "Net-(C3-Pad2)") (class "Default")
      (node (ref "C3") (pin "2") (pinfunction "2_2") (pintype "passive"))
      (node (ref "L1") (pin "2") (pinfunction "2_2") (pintype "passive"))
      (node (ref "P2") (pin "1") (pinfunction "1_1") (pintype "passive"))
    )
    (net (code "47") (name "Net-(C6-Pad2)") (class "Default")
      (node (ref "C6") (pin "2") (pinfunction "2_2") (pintype "passive"))
      (node (ref "L2") (pin "2") (pinfunction "2_2") (pintype "passive"))
      (node (ref "L4") (pin "2") (pinfunction "2_2") (pintype "passive"))
      (node (ref "P2") (pin "2") (pinfunction "2_2") (pintype "passive"))
    )
    (net (code "48") (name "Net-(C10-Pad1)") (class "Default")
      (node (ref "C10") (pin "1") (pinfunction "1_1") (pintype "passive"))
      (node (ref "R4") (pin "1") (pinfunction "1_1") (pintype "passive"))
    )
    (net (code "49") (name "Net-(D1-A)") (class "Default")
      (node (ref "D1") (pin "1") (pinfunction "A_1") (pintype "passive"))
      (node (ref "P1") (pin "2") (pinfunction "2_2") (pintype "passive"))
    )
    (net (code "50") (name "Net-(D2-A)") (class "Default")
      (node (ref "D2") (pin "1") (pinfunction "A_1") (pintype "passive"))
      (node (ref "R15") (pin "2") (pinfunction "2_2") (pintype "passive"))
    )
    (net (code "51") (name "Net-(D3-A)") (class "Default")
      (node (ref "D3") (pin "1") (pinfunction "A_1") (pintype "passive"))
      (node (ref "R14") (pin "2") (pinfunction "2_2") (pintype "passive"))
    )
    (net (code "52") (name "Net-(D4-A)") (class "Default")
      (node (ref "D4") (pin "1") (pinfunction "A_1") (pintype "passive"))
      (node (ref "R18") (pin "2") (pinfunction "2_2") (pintype "passive"))
    )
    (net (code "53") (name "Net-(P3-RST)") (class "Default")
      (node (ref "P3") (pin "3") (pinfunction "RST_3") (pintype "passive"))
      (node (ref "Q1") (pin "3") (pinfunction "C_3") (pintype "passive"))
    )
    (net (code "54") (name "Net-(Q1-B)") (class "Default")
      (node (ref "Q1") (pin "1") (pinfunction "B_1") (pintype "passive"))
      (node (ref "R5") (pin "2") (pinfunction "2_2") (pintype "passive"))
    )
    (net (code "55") (name "Net-(R2-BOT)") (class "Default")
      (node (ref "R1") (pin "2") (pinfunction "2_2") (pintype "passive"))
      (node (ref "R2") (pin "3") (pinfunction "BOT_3") (pintype "passive"))
      (node (ref "U1") (pin "3") (pinfunction "IN+_3") (pintype "input"))
    )
    (net (code "56") (name "Net-(R2-TAP)") (class "Default")
      (node (ref "R2") (pin "1") (pinfunction "TOP_1") (pintype "passive"))
      (node (ref "R2") (pin "2") (pinfunction "TAP_2") (pintype "passive"))
      (node (ref "R3") (pin "2") (pinfunction "2_2") (pintype "passive"))
      (node (ref "U1") (pin "2") (pinfunction "IN-_2") (pintype "input"))
    )
    (net (code "57") (name "Net-(U1-BYPASS)") (class "Default")
      (node (ref "C7") (pin "2") (pinfunction "2_2") (pintype "passive"))
      (node (ref "U1") (pin "7") (pinfunction "BYPASS_7") (pintype "passive"))
    )
    (net (code "58") (name "Net-(U2-RIGHT)") (class "Default")
      (node (ref "R17") (pin "1") (pinfunction "1_1") (pintype "passive"))
      (node (ref "U2") (pin "7") (pinfunction "RIGHT_7") (pintype "passive"))
    )
    (net (code "59") (name "Net-(U2-SPK_L_M)") (class "Default")
      (node (ref "L2") (pin "1") (pinfunction "1_1") (pintype "passive"))
      (node (ref "U2") (pin "1") (pinfunction "SPK_L_M_1") (pintype "passive"))
    )
    (net (code "60") (name "Net-(U2-SPK_L_P)") (class "Default")
      (node (ref "L1") (pin "1") (pinfunction "1_1") (pintype "passive"))
      (node (ref "U2") (pin "2") (pinfunction "SPK_L_P_2") (pintype "passive"))
    )
    (net (code "61") (name "Net-(U2-SPK_R_P)") (class "Default")
      (node (ref "L4") (pin "1") (pinfunction "1_1") (pintype "passive"))
      (node (ref "U2") (pin "3") (pinfunction "SPK_R_P_3") (pintype "passive"))
    )
    (net (code "62") (name "Net-(U3-AREF)") (class "Default")
      (node (ref "C21") (pin "1") (pinfunction "1_1") (pintype "passive"))
      (node (ref "C35") (pin "2") (pinfunction "2_2") (pintype "passive"))
      (node (ref "L3") (pin "1") (pinfunction "1_1") (pintype "passive"))
      (node (ref "U3") (pin "30") (pinfunction "AVCC_30") (pintype "power_in"))
      (node (ref "U3") (pin "32") (pinfunction "AREF_32") (pintype "power_in"))
    )
    (net (code "63") (name "Net-(U3-PC6_(TOSC1))") (class "Default")
      (node (ref "U3") (pin "28") (pinfunction "PC6_(TOSC1)_28") (pintype "bidirectional"))
      (node (ref "Y2") (pin "2") (pinfunction "OSC2_2") (pintype "passive"))
    )
    (net (code "64") (name "Net-(U3-PC7_(TOSC2))") (class "Default")
      (node (ref "U3") (pin "29") (pinfunction "PC7_(TOSC2)_29") (pintype "bidirectional"))
      (node (ref "Y2") (pin "1") (pinfunction "OSC1_1") (pintype "passive"))
    )
    (net (code "65") (name "Net-(U3-XTAL1)") (class "Default")
      (node (ref "C25") (pin "1") (pinfunction "1_1") (pintype "passive"))
      (node (ref "U3") (pin "13") (pinfunction "XTAL1_13") (pintype "passive"))
      (node (ref "Y1") (pin "2") (pinfunction "OSC2_2") (pintype "passive"))
    )
    (net (code "66") (name "Net-(U3-XTAL2)") (class "Default")
      (node (ref "C26") (pin "1") (pinfunction "1_1") (pintype "passive"))
      (node (ref "U3") (pin "12") (pinfunction "XTAL2_12") (pintype "passive"))
      (node (ref "Y1") (pin "1") (pinfunction "OSC1_1") (pintype "passive"))
    )
    (net (code "67") (name "Net-(U5-MISO)") (class "Default")
      (node (ref "R12") (pin "1") (pinfunction "1_1") (pintype "passive"))
      (node (ref "U5") (pin "13") (pinfunction "MISO_13") (pintype "passive"))
    )
    (net (code "68") (name "Net-(U5-MOSI)") (class "Default")
      (node (ref "R11") (pin "1") (pinfunction "1_1") (pintype "passive"))
      (node (ref "U5") (pin "14") (pinfunction "MOSI_14") (pintype "passive"))
    )
    (net (code "69") (name "Net-(U5-SCK)") (class "Default")
      (node (ref "R13") (pin "1") (pinfunction "1_1") (pintype "passive"))
      (node (ref "U5") (pin "12") (pinfunction "SCK_12") (pintype "passive"))
    )
    (net (code "70") (name "VCC") (class "Default")
      (node (ref "C11") (pin "1") (pinfunction "1_1") (pintype "passive"))
      (node (ref "C12") (pin "2") (pinfunction "2_2") (pintype "passive"))
      (node (ref "C19") (pin "1") (pinfunction "1_1") (pintype "passive"))
      (node (ref "C20") (pin "2") (pinfunction "2_2") (pintype "passive"))
      (node (ref "C36") (pin "2") (pinfunction "2_2") (pintype "passive"))
      (node (ref "C4") (pin "1") (pinfunction "1_1") (pintype "passive"))
      (node (ref "C5") (pin "2") (pinfunction "2_2") (pintype "passive"))
      (node (ref "C8") (pin "1") (pinfunction "1_1") (pintype "passive"))
      (node (ref "C9") (pin "2") (pinfunction "2_2") (pintype "passive"))
      (node (ref "D1") (pin "2") (pinfunction "K_2") (pintype "passive"))
      (node (ref "L3") (pin "2") (pinfunction "2_2") (pintype "passive"))
      (node (ref "P3") (pin "2") (pinfunction "VCC_2") (pintype "passive"))
      (node (ref "P5") (pin "1") (pinfunction "1_1") (pintype "passive"))
      (node (ref "P8") (pin "9") (pinfunction "9_9") (pintype "passive"))
      (node (ref "R10") (pin "2") (pinfunction "2_2") (pintype "passive"))
      (node (ref "R14") (pin "1") (pinfunction "1_1") (pintype "passive"))
      (node (ref "R6") (pin "2") (pinfunction "2_2") (pintype "passive"))
      (node (ref "R7") (pin "2") (pinfunction "2_2") (pintype "passive"))
      (node (ref "R8") (pin "2") (pinfunction "2_2") (pintype "passive"))
      (node (ref "R9") (pin "2") (pinfunction "2_2") (pintype "passive"))
      (node (ref "U1") (pin "6") (pinfunction "VS_6") (pintype "power_in"))
      (node (ref "U2") (pin "8") (pinfunction "VCC_8") (pintype "passive"))
      (node (ref "U3") (pin "10") (pinfunction "VCC_10") (pintype "power_in"))
      (node (ref "U4") (pin "3") (pinfunction "IN_3") (pintype "power_in"))
    )
    (net (code "71") (name "unconnected-(P3-DTR-Pad11)") (class "Default")
      (node (ref "P3") (pin "11") (pinfunction "DTR_11") (pintype "passive+no_connect"))
    )
    (net (code "72") (name "unconnected-(P5-Pad9)") (class "Default")
      (node (ref "P5") (pin "9") (pinfunction "9_9") (pintype "passive+no_connect"))
    )
    (net (code "73") (name "unconnected-(P5-Pad10)") (class "Default")
      (node (ref "P5") (pin "10") (pinfunction "10_10") (pintype "passive+no_connect"))
    )
    (net (code "74") (name "unconnected-(P6-Pad2)") (class "Default")
      (node (ref "P6") (pin "2") (pinfunction "2_2") (pintype "passive+no_connect"))
    )
    (net (code "75") (name "unconnected-(P6-Pad9)") (class "Default")
      (node (ref "P6") (pin "9") (pinfunction "9_9") (pintype "passive+no_connect"))
    )
    (net (code "76") (name "unconnected-(U1-GAIN-Pad1)") (class "Default")
      (node (ref "U1") (pin "1") (pinfunction "GAIN_1") (pintype "passive"))
    )
    (net (code "77") (name "unconnected-(U1-GAIN-Pad8)") (class "Default")
      (node (ref "U1") (pin "8") (pinfunction "GAIN_8") (pintype "passive"))
    )
    (net (code "78") (name "unconnected-(U2-SPK_R_M-Pad4)") (class "Default")
      (node (ref "U2") (pin "4") (pinfunction "SPK_R_M_4") (pintype "passive+no_connect"))
    )
    (net (code "79") (name "unconnected-(U5-DIO1-Pad6)") (class "Default")
      (node (ref "U5") (pin "6") (pinfunction "DIO1_6") (pintype "passive+no_connect"))
    )
    (net (code "80") (name "unconnected-(U5-DIO2-Pad7)") (class "Default")
      (node (ref "U5") (pin "7") (pinfunction "DIO2_7") (pintype "passive+no_connect"))
    )
    (net (code "81") (name "unconnected-(U5-DIO3-Pad8)") (class "Default")
      (node (ref "U5") (pin "8") (pinfunction "DIO3_8") (pintype "passive+no_connect"))
    )
    (net (code "82") (name "unconnected-(U5-DIO4-Pad10)") (class "Default")
      (node (ref "U5") (pin "10") (pinfunction "DIO4_10") (pintype "passive+no_connect"))
    )
    (net (code "83") (name "unconnected-(U5-DIO5-Pad11)") (class "Default")
      (node (ref "U5") (pin "11") (pinfunction "DIO5_11") (pintype "passive+no_connect"))
    )
  )
)
